# Main_Sheet.net
KiCad netlist of a schematic drawn in Altium Designer
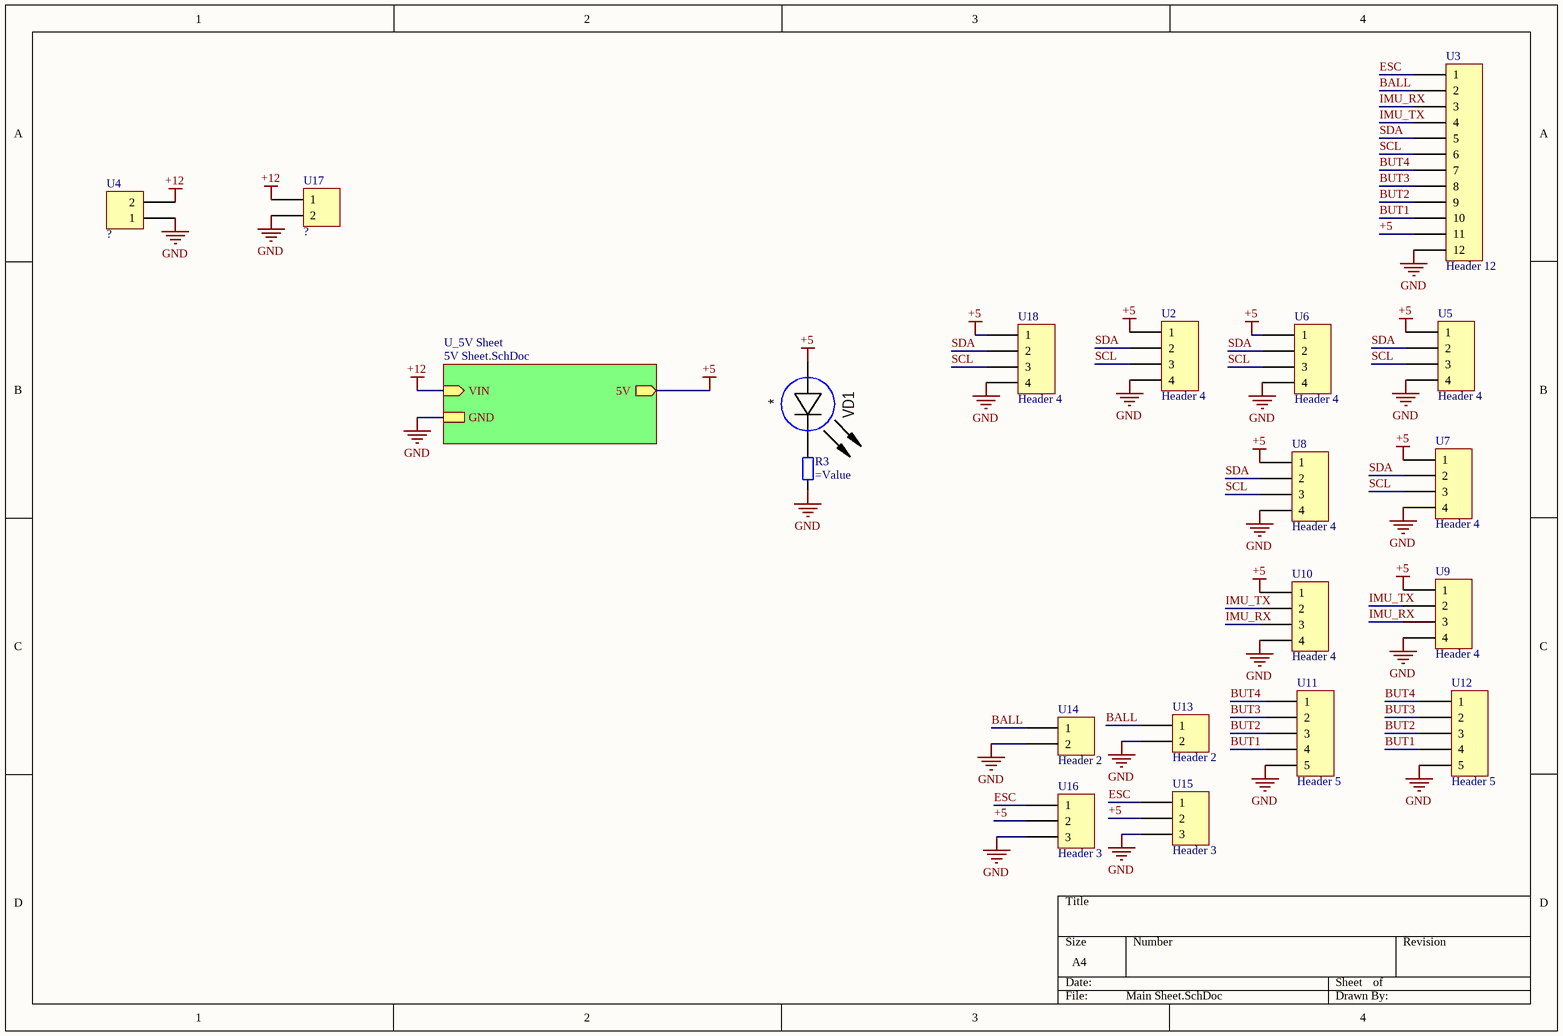
[diagram p0: Main Sheet.SchDoc]

(export (version "E")
  (design (tool "Eeschema 10.0.6"))
  (components
    (comp (ref "R3")
      (value "~")
      (footprint "res0402")
      (libsource (lib "AlexChistiakov") (part "Resistor SMD"))
    )
    (comp (ref "U2")
      (value "Header 4")
      (footprint "4x2.54")
      (libsource (lib "AlexChistiakov") (part "Header 4"))
    )
    (comp (ref "U3")
      (value "Header 12")
      (footprint "12x1.27")
      (libsource (lib "AlexChistiakov") (part "Header 12"))
    )
    (comp (ref "U4")
      (value "?")
      (footprint "XT30")
      (libsource (lib "AlexChistiakov") (part "Power connectors"))
    )
    (comp (ref "U5")
      (value "Header 4")
      (footprint "4x2.54")
      (libsource (lib "AlexChistiakov") (part "Header 4"))
    )
    (comp (ref "U6")
      (value "Header 4")
      (footprint "4x1.27")
      (libsource (lib "AlexChistiakov") (part "Header 4"))
    )
    (comp (ref "U7")
      (value "Header 4")
      (footprint "4x2.54")
      (libsource (lib "AlexChistiakov") (part "Header 4"))
    )
    (comp (ref "U8")
      (value "Header 4")
      (footprint "4x1.27")
      (libsource (lib "AlexChistiakov") (part "Header 4"))
    )
    (comp (ref "U9")
      (value "Header 4")
      (footprint "4x2.54")
      (libsource (lib "AlexChistiakov") (part "Header 4"))
    )
    (comp (ref "U10")
      (value "Header 4")
      (footprint "4x1.27")
      (libsource (lib "AlexChistiakov") (part "Header 4"))
    )
    (comp (ref "U11")
      (value "Header 5")
      (footprint "5x1.27")
      (libsource (lib "AlexChistiakov") (part "Header 5"))
    )
    (comp (ref "U12")
      (value "Header 5")
      (footprint "5x2.54")
      (libsource (lib "AlexChistiakov") (part "Header 5"))
    )
    (comp (ref "U13")
      (value "Header 2")
      (footprint "2x2.54")
      (libsource (lib "AlexChistiakov") (part "Header 2"))
    )
    (comp (ref "U14")
      (value "Header 2")
      (footprint "2x1.27")
      (libsource (lib "AlexChistiakov") (part "Header 2"))
    )
    (comp (ref "U15")
      (value "Header 3")
      (footprint "3x2.54")
      (libsource (lib "AlexChistiakov") (part "Header 3"))
    )
    (comp (ref "U16")
      (value "Header 3")
      (footprint "3x1.27")
      (libsource (lib "AlexChistiakov") (part "Header 3"))
    )
    (comp (ref "U17") (value "?") (footprint "XT30") (libsource (lib "") (part "Power connectors_1")))
    (comp (ref "U18")
      (value "Header 4")
      (footprint "4x1.27")
      (libsource (lib "AlexChistiakov") (part "Header 4"))
    )
    (comp (ref "VD1") (value "*") (footprint "CH0603LB") (libsource (lib "Discrete") (part "LED")))
  )
  (nets
    (net (code "1") (name "+5") (class "Default")
      (node (ref "U10") (pin "1") (pinfunction "1_1") (pintype "power_in"))
      (node (ref "U15") (pin "2") (pinfunction "2_2") (pintype "power_in"))
      (node (ref "U16") (pin "2") (pinfunction "2_2") (pintype "power_in"))
      (node (ref "U18") (pin "1") (pinfunction "1_1") (pintype "power_in"))
      (node (ref "U2") (pin "1") (pinfunction "1_1") (pintype "power_in"))
      (node (ref "U3") (pin "11") (pinfunction "11_11") (pintype "power_in"))
      (node (ref "U5") (pin "1") (pinfunction "1_1") (pintype "power_in"))
      (node (ref "U6") (pin "1") (pinfunction "1_1") (pintype "power_in"))
      (node (ref "U7") (pin "1") (pinfunction "1_1") (pintype "power_in"))
      (node (ref "U8") (pin "1") (pinfunction "1_1") (pintype "power_in"))
      (node (ref "U9") (pin "1") (pinfunction "1_1") (pintype "power_in"))
      (node (ref "VD1") (pin "1") (pinfunction "A_1") (pintype "passive"))
    )
    (net (code "2") (name "+12") (class "Default")
      (node (ref "U17") (pin "1") (pinfunction "1_1") (pintype "power_in"))
      (node (ref "U4") (pin "2") (pinfunction "2_2") (pintype "power_in"))
    )
    (net (code "3") (name "/BALL") (class "Default")
      (node (ref "U13") (pin "1") (pinfunction "1_1") (pintype "power_in"))
      (node (ref "U14") (pin "1") (pinfunction "1_1") (pintype "power_in"))
      (node (ref "U3") (pin "2") (pinfunction "2_2") (pintype "power_in"))
    )
    (net (code "4") (name "/BUT1") (class "Default")
      (node (ref "U11") (pin "4") (pinfunction "4_4") (pintype "power_in"))
      (node (ref "U12") (pin "4") (pinfunction "4_4") (pintype "power_in"))
      (node (ref "U3") (pin "10") (pinfunction "10_10") (pintype "power_in"))
    )
    (net (code "5") (name "/BUT2") (class "Default")
      (node (ref "U11") (pin "3") (pinfunction "3_3") (pintype "power_in"))
      (node (ref "U12") (pin "3") (pinfunction "3_3") (pintype "power_in"))
      (node (ref "U3") (pin "9") (pinfunction "9_9") (pintype "power_in"))
    )
    (net (code "6") (name "/BUT3") (class "Default")
      (node (ref "U11") (pin "2") (pinfunction "2_2") (pintype "power_in"))
      (node (ref "U12") (pin "2") (pinfunction "2_2") (pintype "power_in"))
      (node (ref "U3") (pin "8") (pinfunction "8_8") (pintype "power_in"))
    )
    (net (code "7") (name "/BUT4") (class "Default")
      (node (ref "U11") (pin "1") (pinfunction "1_1") (pintype "power_in"))
      (node (ref "U12") (pin "1") (pinfunction "1_1") (pintype "power_in"))
      (node (ref "U3") (pin "7") (pinfunction "7_7") (pintype "power_in"))
    )
    (net (code "8") (name "/ESC") (class "Default")
      (node (ref "U15") (pin "1") (pinfunction "1_1") (pintype "power_in"))
      (node (ref "U16") (pin "1") (pinfunction "1_1") (pintype "power_in"))
      (node (ref "U3") (pin "1") (pinfunction "1_1") (pintype "power_in"))
    )
    (net (code "9") (name "/IMU_RX") (class "Default")
      (node (ref "U10") (pin "3") (pinfunction "3_3") (pintype "power_in"))
      (node (ref "U3") (pin "3") (pinfunction "3_3") (pintype "power_in"))
      (node (ref "U9") (pin "3") (pinfunction "3_3") (pintype "power_in"))
    )
    (net (code "10") (name "/IMU_TX") (class "Default")
      (node (ref "U10") (pin "2") (pinfunction "2_2") (pintype "power_in"))
      (node (ref "U3") (pin "4") (pinfunction "4_4") (pintype "power_in"))
      (node (ref "U9") (pin "2") (pinfunction "2_2") (pintype "power_in"))
    )
    (net (code "11") (name "/SCL") (class "Default")
      (node (ref "U18") (pin "3") (pinfunction "3_3") (pintype "power_in"))
      (node (ref "U2") (pin "3") (pinfunction "3_3") (pintype "power_in"))
      (node (ref "U3") (pin "6") (pinfunction "6_6") (pintype "power_in"))
      (node (ref "U5") (pin "3") (pinfunction "3_3") (pintype "power_in"))
      (node (ref "U6") (pin "3") (pinfunction "3_3") (pintype "power_in"))
      (node (ref "U7") (pin "3") (pinfunction "3_3") (pintype "power_in"))
      (node (ref "U8") (pin "3") (pinfunction "3_3") (pintype "power_in"))
    )
    (net (code "12") (name "/SDA") (class "Default")
      (node (ref "U18") (pin "2") (pinfunction "2_2") (pintype "power_in"))
      (node (ref "U2") (pin "2") (pinfunction "2_2") (pintype "power_in"))
      (node (ref "U3") (pin "5") (pinfunction "5_5") (pintype "power_in"))
      (node (ref "U5") (pin "2") (pinfunction "2_2") (pintype "power_in"))
      (node (ref "U6") (pin "2") (pinfunction "2_2") (pintype "power_in"))
      (node (ref "U7") (pin "2") (pinfunction "2_2") (pintype "power_in"))
      (node (ref "U8") (pin "2") (pinfunction "2_2") (pintype "power_in"))
    )
    (net (code "13") (name "GND") (class "Default")
      (node (ref "R3") (pin "1") (pinfunction "1_1") (pintype "passive"))
      (node (ref "U10") (pin "4") (pinfunction "4_4") (pintype "power_in"))
      (node (ref "U11") (pin "5") (pinfunction "5_5") (pintype "power_in"))
      (node (ref "U12") (pin "5") (pinfunction "5_5") (pintype "power_in"))
      (node (ref "U13") (pin "2") (pinfunction "2_2") (pintype "power_in"))
      (node (ref "U14") (pin "2") (pinfunction "2_2") (pintype "power_in"))
      (node (ref "U15") (pin "3") (pinfunction "3_3") (pintype "power_in"))
      (node (ref "U16") (pin "3") (pinfunction "3_3") (pintype "power_in"))
      (node (ref "U17") (pin "2") (pinfunction "2_2") (pintype "power_in"))
      (node (ref "U18") (pin "4") (pinfunction "4_4") (pintype "power_in"))
      (node (ref "U2") (pin "4") (pinfunction "4_4") (pintype "power_in"))
      (node (ref "U3") (pin "12") (pinfunction "12_12") (pintype "power_in"))
      (node (ref "U4") (pin "1") (pinfunction "1_1") (pintype "power_in"))
      (node (ref "U5") (pin "4") (pinfunction "4_4") (pintype "power_in"))
      (node (ref "U6") (pin "4") (pinfunction "4_4") (pintype "power_in"))
      (node (ref "U7") (pin "4") (pinfunction "4_4") (pintype "power_in"))
      (node (ref "U8") (pin "4") (pinfunction "4_4") (pintype "power_in"))
      (node (ref "U9") (pin "4") (pinfunction "4_4") (pintype "power_in"))
    )
    (net (code "14") (name "Net-(VD1-C)") (class "Default")
      (node (ref "R3") (pin "2") (pinfunction "2_2") (pintype "passive"))
      (node (ref "VD1") (pin "2") (pinfunction "C_2") (pintype "passive"))
    )
  )
)
